# 140701_AriloTX_REV2_0_0.net
KiCad netlist of a schematic drawn in EAGLE
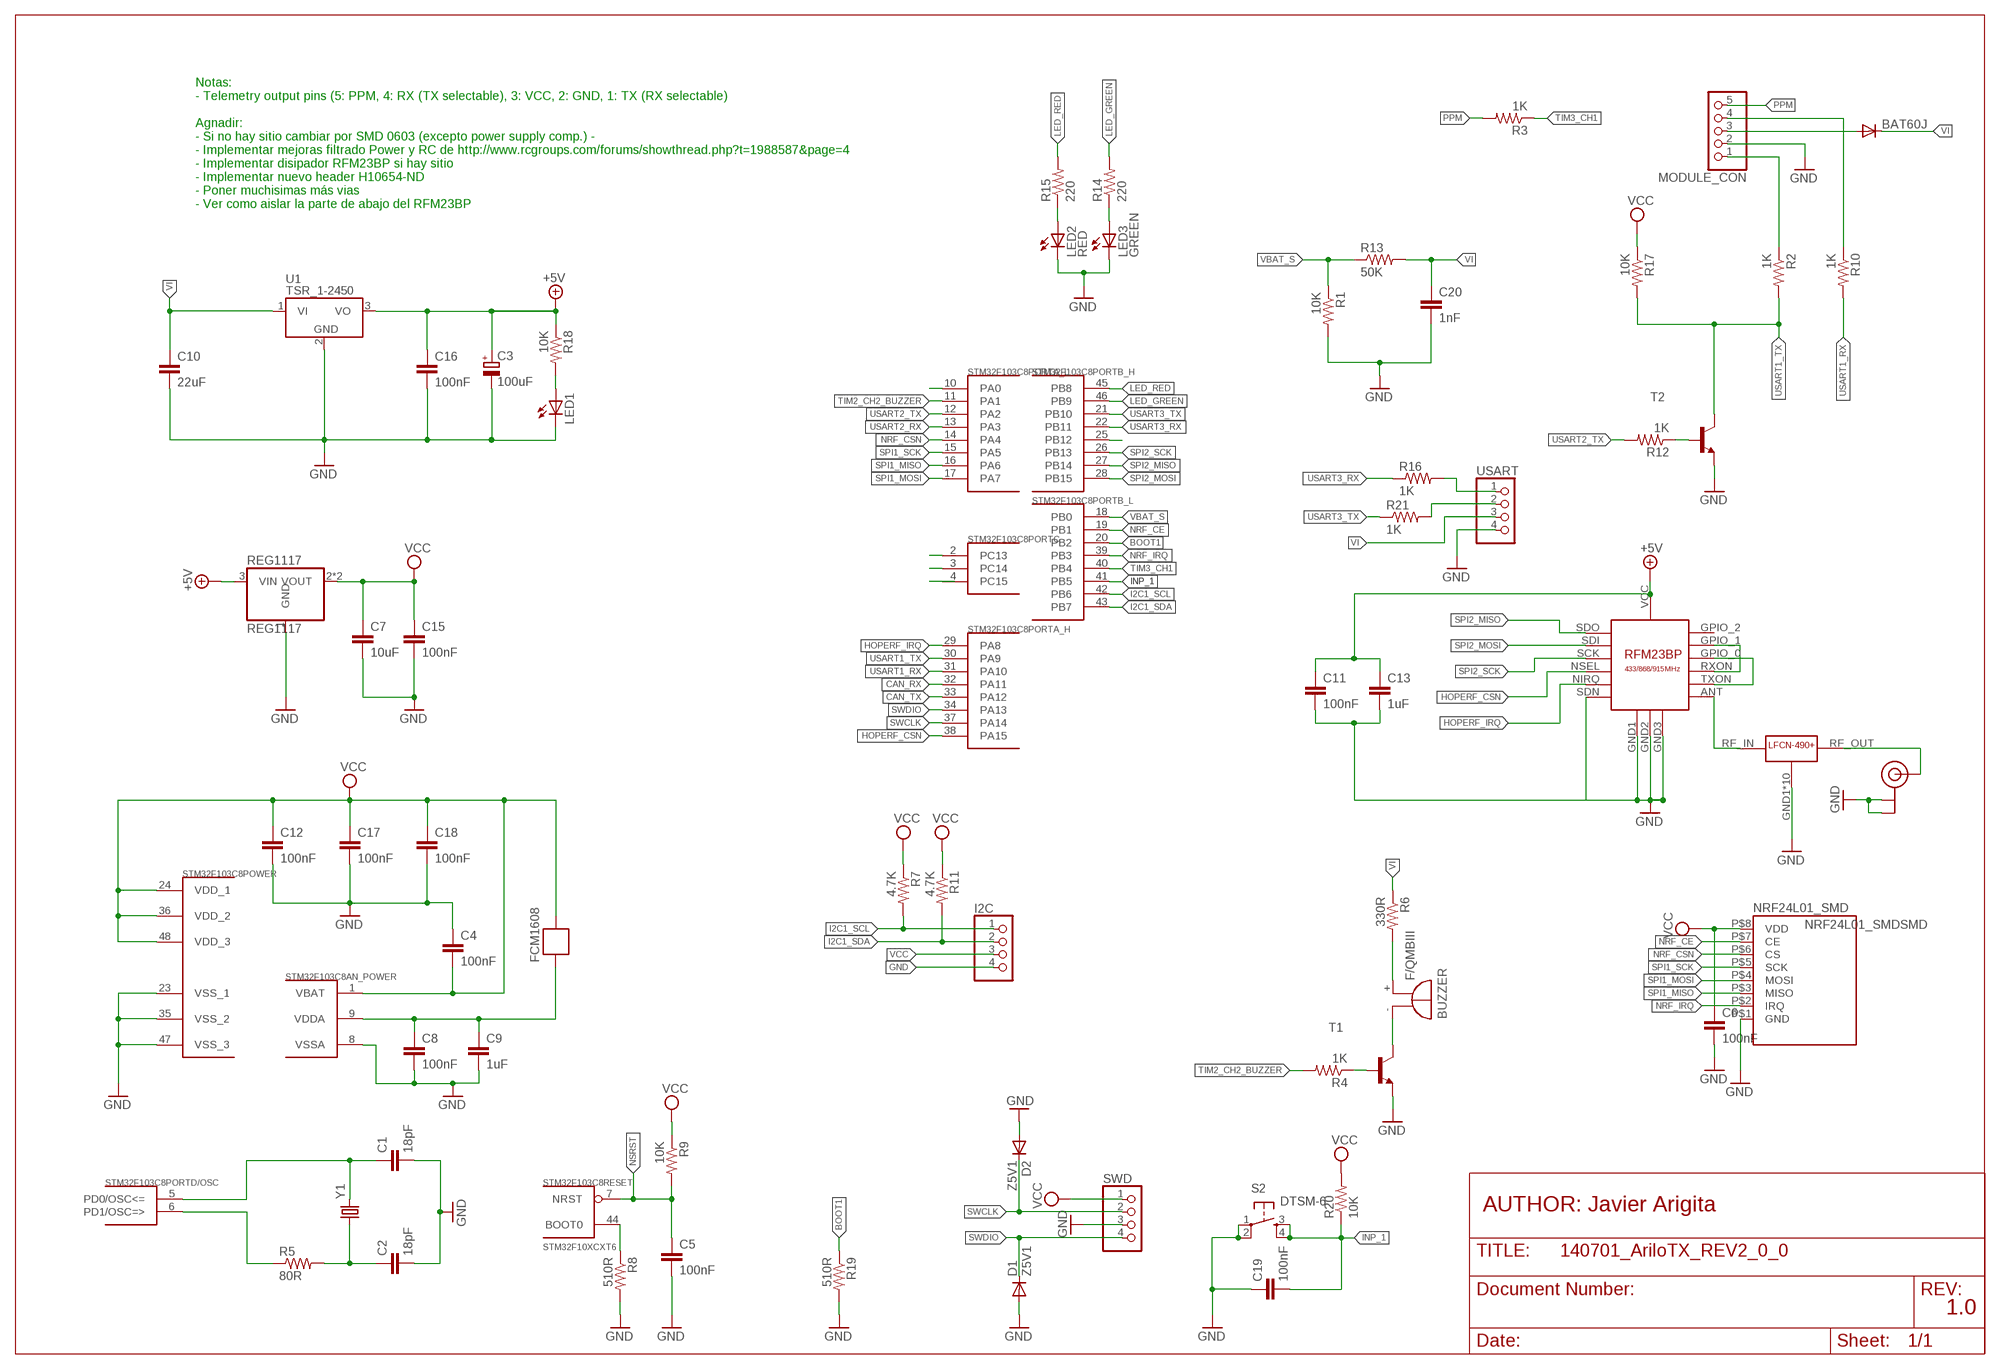
[diagram p0: schematic, sheet 1]

(export (version "E")
  (design (tool "Eeschema 10.0.6"))
  (components
    (comp (ref "BAT60J")
      (value "DIODE-SOD323-R")
      (footprint "eagle-import:SOD323-R")
      (libsource (lib "eagle-import") (part "DIODE-SOD323-R"))
    )
    (comp (ref "BUZZER")
      (value "F/QMBIII")
      (footprint "eagle-import:F_QMBIII")
      (libsource (lib "eagle-import") (part "F/QMBIII"))
    )
    (comp (ref "C1")
      (value "18pF")
      (footprint "eagle-import:C0805")
      (libsource (lib "eagle-import") (part "C-EUC0805"))
    )
    (comp (ref "C2")
      (value "18pF")
      (footprint "eagle-import:C0805")
      (libsource (lib "eagle-import") (part "C-EUC0805"))
    )
    (comp (ref "C3")
      (value "100uF")
      (footprint "eagle-import:SMC_B")
      (libsource (lib "eagle-import") (part "CPOL-EUSMCB"))
    )
    (comp (ref "C4")
      (value "100nF")
      (footprint "eagle-import:C0805")
      (libsource (lib "eagle-import") (part "C-EUC0805"))
    )
    (comp (ref "C5")
      (value "100nF")
      (footprint "eagle-import:C0805")
      (libsource (lib "eagle-import") (part "C-EUC0805"))
    )
    (comp (ref "C6")
      (value "100nF")
      (footprint "eagle-import:C0805")
      (libsource (lib "eagle-import") (part "C-EUC0805"))
    )
    (comp (ref "C7")
      (value "10uF")
      (footprint "eagle-import:C0805")
      (libsource (lib "eagle-import") (part "C-EUC0805"))
    )
    (comp (ref "C8")
      (value "100nF")
      (footprint "eagle-import:C0805")
      (libsource (lib "eagle-import") (part "C-EUC0805"))
    )
    (comp (ref "C9")
      (value "1uF")
      (footprint "eagle-import:C3216")
      (libsource (lib "eagle-import") (part "resistor_C-EUC3216"))
    )
    (comp (ref "C10")
      (value "22uF")
      (footprint "eagle-import:C3216")
      (libsource (lib "eagle-import") (part "resistor_C-EUC3216"))
    )
    (comp (ref "C11")
      (value "100nF")
      (footprint "eagle-import:C0805")
      (libsource (lib "eagle-import") (part "C-EUC0805"))
    )
    (comp (ref "C12")
      (value "100nF")
      (footprint "eagle-import:C0805")
      (libsource (lib "eagle-import") (part "C-EUC0805"))
    )
    (comp (ref "C13")
      (value "1uF")
      (footprint "eagle-import:C3216")
      (libsource (lib "eagle-import") (part "resistor_C-EUC3216"))
    )
    (comp (ref "C15")
      (value "100nF")
      (footprint "eagle-import:C0805")
      (libsource (lib "eagle-import") (part "C-EUC0805"))
    )
    (comp (ref "C16")
      (value "100nF")
      (footprint "eagle-import:C0805")
      (libsource (lib "eagle-import") (part "C-EUC0805"))
    )
    (comp (ref "C17")
      (value "100nF")
      (footprint "eagle-import:C0805")
      (libsource (lib "eagle-import") (part "C-EUC0805"))
    )
    (comp (ref "C18")
      (value "100nF")
      (footprint "eagle-import:C0805")
      (libsource (lib "eagle-import") (part "C-EUC0805"))
    )
    (comp (ref "C19")
      (value "100nF")
      (footprint "eagle-import:C0805")
      (libsource (lib "eagle-import") (part "C-EUC0805"))
    )
    (comp (ref "C20")
      (value "1nF")
      (footprint "eagle-import:C0805")
      (libsource (lib "eagle-import") (part "C-EUC0805"))
    )
    (comp (ref "D1")
      (value "Z5V1")
      (footprint "eagle-import:SOD323-R")
      (libsource (lib "eagle-import") (part "DIODE-SOD323-R"))
    )
    (comp (ref "D2")
      (value "Z5V1")
      (footprint "eagle-import:SOD323-R")
      (libsource (lib "eagle-import") (part "DIODE-SOD323-R"))
    )
    (comp (ref "FCM1608")
      (value "FERRITE-BEAD")
      (footprint "eagle-import:R0603")
      (libsource (lib "eagle-import") (part "FERRITE-BEAD"))
    )
    (comp (ref "I2C")
      (value "PINHD-1X4")
      (footprint "eagle-import:1X04")
      (libsource (lib "eagle-import") (part "PINHD-1X4"))
    )
    (comp (ref "LED1")
      (value "LED0805")
      (footprint "eagle-import:CHIPLED_0805")
      (libsource (lib "eagle-import") (part "LED0805"))
    )
    (comp (ref "LED2")
      (value "RED")
      (footprint "eagle-import:CHIP-LED0805")
      (libsource (lib "eagle-import") (part "LEDCHIP-LED0805"))
    )
    (comp (ref "LED3")
      (value "GREEN")
      (footprint "eagle-import:CHIP-LED0805")
      (libsource (lib "eagle-import") (part "LEDCHIP-LED0805"))
    )
    (comp (ref "MODULE_CON")
      (value "PINHD-1X5")
      (footprint "eagle-import:1X05")
      (libsource (lib "eagle-import") (part "PINHD-1X5"))
    )
    (comp (ref "NRF24L01_SMD")
      (value "NRF24L01_SMDSMD")
      (footprint "eagle-import:NRF24L01_SMD")
      (libsource (lib "eagle-import") (part "NRF24L01_SMDSMD"))
    )
    (comp (ref "R1")
      (value "10K")
      (footprint "eagle-import:R0805")
      (libsource (lib "eagle-import") (part "RESISTOR0805"))
    )
    (comp (ref "R2")
      (value "1K")
      (footprint "eagle-import:R0805")
      (libsource (lib "eagle-import") (part "RESISTOR0805"))
    )
    (comp (ref "R3")
      (value "1K")
      (footprint "eagle-import:R0805")
      (libsource (lib "eagle-import") (part "RESISTOR0805"))
    )
    (comp (ref "R4")
      (value "1K")
      (footprint "eagle-import:R0805")
      (libsource (lib "eagle-import") (part "RESISTOR0805"))
    )
    (comp (ref "R5")
      (value "80R")
      (footprint "eagle-import:R0805")
      (libsource (lib "eagle-import") (part "RESISTOR0805"))
    )
    (comp (ref "R6")
      (value "330R")
      (footprint "eagle-import:R0805")
      (libsource (lib "eagle-import") (part "RESISTOR0805"))
    )
    (comp (ref "R7")
      (value "4.7K")
      (footprint "eagle-import:R0805")
      (libsource (lib "eagle-import") (part "RESISTOR0805"))
    )
    (comp (ref "R8")
      (value "510R")
      (footprint "eagle-import:R0805")
      (libsource (lib "eagle-import") (part "RESISTOR0805"))
    )
    (comp (ref "R9")
      (value "10K")
      (footprint "eagle-import:R0805")
      (libsource (lib "eagle-import") (part "RESISTOR0805"))
    )
    (comp (ref "R10")
      (value "1K")
      (footprint "eagle-import:R0805")
      (libsource (lib "eagle-import") (part "RESISTOR0805"))
    )
    (comp (ref "R11")
      (value "4.7K")
      (footprint "eagle-import:R0805")
      (libsource (lib "eagle-import") (part "RESISTOR0805"))
    )
    (comp (ref "R12")
      (value "1K")
      (footprint "eagle-import:R0805")
      (libsource (lib "eagle-import") (part "RESISTOR0805"))
    )
    (comp (ref "R13")
      (value "50K")
      (footprint "eagle-import:R0805")
      (libsource (lib "eagle-import") (part "RESISTOR0805"))
    )
    (comp (ref "R14")
      (value "220")
      (footprint "eagle-import:R0805")
      (libsource (lib "eagle-import") (part "RESISTOR0805"))
    )
    (comp (ref "R15")
      (value "220")
      (footprint "eagle-import:R0805")
      (libsource (lib "eagle-import") (part "RESISTOR0805"))
    )
    (comp (ref "R16")
      (value "1K")
      (footprint "eagle-import:R0805")
      (libsource (lib "eagle-import") (part "RESISTOR0805"))
    )
    (comp (ref "R17")
      (value "10K")
      (footprint "eagle-import:R0805")
      (libsource (lib "eagle-import") (part "RESISTOR0805"))
    )
    (comp (ref "R18")
      (value "10K")
      (footprint "eagle-import:R0805")
      (libsource (lib "eagle-import") (part "RESISTOR0805"))
    )
    (comp (ref "R19")
      (value "510R")
      (footprint "eagle-import:R0805")
      (libsource (lib "eagle-import") (part "RESISTOR0805"))
    )
    (comp (ref "R20")
      (value "10K")
      (footprint "eagle-import:R0805")
      (libsource (lib "eagle-import") (part "RESISTOR0805"))
    )
    (comp (ref "R21")
      (value "1K")
      (footprint "eagle-import:R0805")
      (libsource (lib "eagle-import") (part "RESISTOR0805"))
    )
    (comp (ref "REG1117")
      (value "REG1117")
      (footprint "eagle-import:SOT223")
      (libsource (lib "eagle-import") (part "REG1117"))
    )
    (comp (ref "S2")
      (value "DTSM-6")
      (footprint "eagle-import:DTSM-6")
      (libsource (lib "eagle-import") (part "DTSM-6"))
    )
    (comp (ref "STM32F103C8")
      (value "STM32F10XCXT6")
      (footprint "eagle-import:TQFP48")
      (libsource (lib "eagle-import") (part "STM32F10XCXT6"))
    )
    (comp (ref "SWD")
      (value "PINHD-1X4")
      (footprint "eagle-import:1X04")
      (libsource (lib "eagle-import") (part "PINHD-1X4"))
    )
    (comp (ref "T1")
      (value "BC848-NPN-SOT23-BEC")
      (footprint "eagle-import:SOT23-BEC")
      (libsource (lib "eagle-import") (part "-NPN-SOT23-BECBC848"))
    )
    (comp (ref "T2")
      (value "BC848-NPN-SOT23-BEC")
      (footprint "eagle-import:SOT23-BEC")
      (libsource (lib "eagle-import") (part "-NPN-SOT23-BECBC848"))
    )
    (comp (ref "U$1")
      (value "RFM23BP")
      (footprint "eagle-import:RFM23BP")
      (libsource (lib "eagle-import") (part "RFM23BP"))
    )
    (comp (ref "U$2")
      (value "LFCN490+")
      (footprint "eagle-import:LFCN490+")
      (libsource (lib "eagle-import") (part "LFCN490+"))
    )
    (comp (ref "U$3")
      (value "U.FL")
      (footprint "eagle-import:U.FL")
      (libsource (lib "eagle-import") (part "U.FL"))
    )
    (comp (ref "U1")
      (value "TSR_1-2450")
      (footprint "eagle-import:TSR-1")
      (libsource (lib "eagle-import") (part "TSR_1-2450"))
    )
    (comp (ref "USART")
      (value "PINHD-1X4")
      (footprint "eagle-import:1X04")
      (libsource (lib "eagle-import") (part "PINHD-1X4"))
    )
    (comp (ref "Y1")
      (value "CRYSTAL5X3")
      (footprint "eagle-import:CRYSTAL-SMD-5X3")
      (libsource (lib "eagle-import") (part "CRYSTAL5X3"))
    )
  )
  (nets
    (net (code "1") (name "+5V") (class "Default")
      (node (ref "C11") (pin "1") (pinfunction "1_1") (pintype "passive"))
      (node (ref "C13") (pin "1") (pinfunction "1_1") (pintype "passive"))
      (node (ref "C16") (pin "1") (pinfunction "1_1") (pintype "passive"))
      (node (ref "C3") (pin "+") (pinfunction "+_+") (pintype "passive"))
      (node (ref "R18") (pin "1") (pinfunction "1_1") (pintype "passive"))
      (node (ref "REG1117") (pin "3") (pinfunction "VIN_3") (pintype "input"))
      (node (ref "U$1") (pin "VCC") (pinfunction "VCC_VCC") (pintype "power_in"))
      (node (ref "U1") (pin "3") (pinfunction "VO_3") (pintype "power_in"))
    )
    (net (code "2") (name "BOOT1") (class "Default")
      (node (ref "R19") (pin "1") (pinfunction "1_1") (pintype "passive"))
      (node (ref "STM32F103C8") (pin "20") (pinfunction "PB2_20") (pintype "bidirectional"))
    )
    (net (code "3") (name "CAN_RX") (class "Default")
      (node (ref "STM32F103C8") (pin "32") (pinfunction "PA11_32") (pintype "bidirectional"))
    )
    (net (code "4") (name "CAN_TX") (class "Default")
      (node (ref "STM32F103C8") (pin "33") (pinfunction "PA12_33") (pintype "bidirectional"))
    )
    (net (code "5") (name "GND") (class "Default")
      (node (ref "C1") (pin "2") (pinfunction "2_2") (pintype "passive"))
      (node (ref "C10") (pin "2") (pinfunction "2_2") (pintype "passive"))
      (node (ref "C11") (pin "2") (pinfunction "2_2") (pintype "passive"))
      (node (ref "C12") (pin "2") (pinfunction "2_2") (pintype "passive"))
      (node (ref "C13") (pin "2") (pinfunction "2_2") (pintype "passive"))
      (node (ref "C15") (pin "2") (pinfunction "2_2") (pintype "passive"))
      (node (ref "C16") (pin "2") (pinfunction "2_2") (pintype "passive"))
      (node (ref "C17") (pin "2") (pinfunction "2_2") (pintype "passive"))
      (node (ref "C18") (pin "2") (pinfunction "2_2") (pintype "passive"))
      (node (ref "C19") (pin "1") (pinfunction "1_1") (pintype "passive"))
      (node (ref "C2") (pin "2") (pinfunction "2_2") (pintype "passive"))
      (node (ref "C20") (pin "2") (pinfunction "2_2") (pintype "passive"))
      (node (ref "C3") (pin "-") (pinfunction "-_-") (pintype "passive"))
      (node (ref "C4") (pin "1") (pinfunction "1_1") (pintype "passive"))
      (node (ref "C5") (pin "2") (pinfunction "2_2") (pintype "passive"))
      (node (ref "C6") (pin "2") (pinfunction "2_2") (pintype "passive"))
      (node (ref "C7") (pin "2") (pinfunction "2_2") (pintype "passive"))
      (node (ref "C8") (pin "2") (pinfunction "2_2") (pintype "passive"))
      (node (ref "C9") (pin "2") (pinfunction "2_2") (pintype "passive"))
      (node (ref "D1") (pin "A") (pinfunction "A_A") (pintype "passive"))
      (node (ref "D2") (pin "A") (pinfunction "A_A") (pintype "passive"))
      (node (ref "I2C") (pin "4") (pinfunction "4_4") (pintype "passive"))
      (node (ref "LED1") (pin "C") (pinfunction "C_C") (pintype "passive"))
      (node (ref "LED2") (pin "C") (pinfunction "C_C") (pintype "passive"))
      (node (ref "LED3") (pin "C") (pinfunction "C_C") (pintype "passive"))
      (node (ref "MODULE_CON") (pin "2") (pinfunction "2_2") (pintype "passive"))
      (node (ref "NRF24L01_SMD") (pin "P$1") (pinfunction "GND_P$1") (pintype "power_in"))
      (node (ref "R1") (pin "2") (pinfunction "2_2") (pintype "passive"))
      (node (ref "R19") (pin "2") (pinfunction "2_2") (pintype "passive"))
      (node (ref "R8") (pin "2") (pinfunction "2_2") (pintype "passive"))
      (node (ref "REG1117") (pin "1") (pinfunction "GND_1") (pintype "power_in"))
      (node (ref "S2") (pin "1") (pinfunction "1_1") (pintype "passive"))
      (node (ref "S2") (pin "2") (pinfunction "2_2") (pintype "passive"))
      (node (ref "STM32F103C8") (pin "23") (pinfunction "VSS_1_23") (pintype "power_in"))
      (node (ref "STM32F103C8") (pin "35") (pinfunction "VSS_2_35") (pintype "power_in"))
      (node (ref "STM32F103C8") (pin "47") (pinfunction "VSS_3_47") (pintype "power_in"))
      (node (ref "STM32F103C8") (pin "8") (pinfunction "VSSA_8") (pintype "power_in"))
      (node (ref "SWD") (pin "3") (pinfunction "3_3") (pintype "passive"))
      (node (ref "T1") (pin "E") (pinfunction "E_E") (pintype "passive"))
      (node (ref "T2") (pin "E") (pinfunction "E_E") (pintype "passive"))
      (node (ref "U$1") (pin "GND1") (pinfunction "GND1_GND1") (pintype "power_in"))
      (node (ref "U$1") (pin "GND2") (pinfunction "GND2_GND2") (pintype "power_in"))
      (node (ref "U$1") (pin "GND3") (pinfunction "GND3_GND3") (pintype "power_in"))
      (node (ref "U$1") (pin "SDN") (pinfunction "SDN_SDN") (pintype "bidirectional"))
      (node (ref "U$2") (pin "GND1") (pinfunction "GND_GND1") (pintype "bidirectional"))
      (node (ref "U$2") (pin "GND10") (pinfunction "GND_GND10") (pintype "bidirectional"))
      (node (ref "U$2") (pin "GND2") (pinfunction "GND_GND2") (pintype "bidirectional"))
      (node (ref "U$2") (pin "GND3") (pinfunction "GND_GND3") (pintype "bidirectional"))
      (node (ref "U$2") (pin "GND4") (pinfunction "GND_GND4") (pintype "bidirectional"))
      (node (ref "U$2") (pin "GND5") (pinfunction "GND_GND5") (pintype "bidirectional"))
      (node (ref "U$2") (pin "GND6") (pinfunction "GND_GND6") (pintype "bidirectional"))
      (node (ref "U$2") (pin "GND7") (pinfunction "GND_GND7") (pintype "bidirectional"))
      (node (ref "U$2") (pin "GND8") (pinfunction "GND_GND8") (pintype "bidirectional"))
      (node (ref "U$2") (pin "GND9") (pinfunction "GND_GND9") (pintype "bidirectional"))
      (node (ref "U$3") (pin "P$1") (pinfunction "GND_P$1") (pintype "bidirectional"))
      (node (ref "U$3") (pin "P$2") (pinfunction "GND_P$2") (pintype "bidirectional"))
      (node (ref "U1") (pin "2") (pinfunction "GND_2") (pintype "power_in"))
      (node (ref "USART") (pin "4") (pinfunction "4_4") (pintype "passive"))
    )
    (net (code "6") (name "HOPERF_CSN") (class "Default")
      (node (ref "STM32F103C8") (pin "38") (pinfunction "PA15_38") (pintype "bidirectional"))
      (node (ref "U$1") (pin "NSEL") (pinfunction "NSEL_NSEL") (pintype "bidirectional"))
    )
    (net (code "7") (name "HOPERF_IRQ") (class "Default")
      (node (ref "STM32F103C8") (pin "29") (pinfunction "PA8_29") (pintype "bidirectional"))
      (node (ref "U$1") (pin "NIRQ") (pinfunction "NIRQ_NIRQ") (pintype "bidirectional"))
    )
    (net (code "8") (name "I2C1_SCL") (class "Default")
      (node (ref "I2C") (pin "1") (pinfunction "1_1") (pintype "passive"))
      (node (ref "R7") (pin "2") (pinfunction "2_2") (pintype "passive"))
      (node (ref "STM32F103C8") (pin "42") (pinfunction "PB6_42") (pintype "bidirectional"))
    )
    (net (code "9") (name "I2C1_SDA") (class "Default")
      (node (ref "I2C") (pin "2") (pinfunction "2_2") (pintype "passive"))
      (node (ref "R11") (pin "2") (pinfunction "2_2") (pintype "passive"))
      (node (ref "STM32F103C8") (pin "43") (pinfunction "PB7_43") (pintype "bidirectional"))
    )
    (net (code "10") (name "INP_1") (class "Default")
      (node (ref "C19") (pin "2") (pinfunction "2_2") (pintype "passive"))
      (node (ref "R20") (pin "1") (pinfunction "1_1") (pintype "passive"))
      (node (ref "S2") (pin "3") (pinfunction "3_3") (pintype "passive"))
      (node (ref "S2") (pin "4") (pinfunction "4_4") (pintype "passive"))
      (node (ref "STM32F103C8") (pin "41") (pinfunction "PB5_41") (pintype "bidirectional"))
    )
    (net (code "11") (name "LED_GREEN") (class "Default")
      (node (ref "R14") (pin "2") (pinfunction "2_2") (pintype "passive"))
      (node (ref "STM32F103C8") (pin "46") (pinfunction "PB9_46") (pintype "bidirectional"))
    )
    (net (code "12") (name "LED_RED") (class "Default")
      (node (ref "R15") (pin "2") (pinfunction "2_2") (pintype "passive"))
      (node (ref "STM32F103C8") (pin "45") (pinfunction "PB8_45") (pintype "bidirectional"))
    )
    (net (code "13") (name "NRF_CE") (class "Default")
      (node (ref "NRF24L01_SMD") (pin "P$7") (pinfunction "CE_P$7") (pintype "input"))
      (node (ref "STM32F103C8") (pin "19") (pinfunction "PB1_19") (pintype "bidirectional"))
    )
    (net (code "14") (name "NRF_CSN") (class "Default")
      (node (ref "NRF24L01_SMD") (pin "P$6") (pinfunction "CS_P$6") (pintype "input"))
      (node (ref "STM32F103C8") (pin "14") (pinfunction "PA4_14") (pintype "bidirectional"))
    )
    (net (code "15") (name "NRF_IRQ") (class "Default")
      (node (ref "NRF24L01_SMD") (pin "P$2") (pinfunction "IRQ_P$2") (pintype "output"))
      (node (ref "STM32F103C8") (pin "39") (pinfunction "PB3_39") (pintype "bidirectional"))
    )
    (net (code "16") (name "NSRST") (class "Default")
      (node (ref "C5") (pin "1") (pinfunction "1_1") (pintype "passive"))
      (node (ref "R9") (pin "2") (pinfunction "2_2") (pintype "passive"))
      (node (ref "STM32F103C8") (pin "7") (pinfunction "NRST_7") (pintype "input"))
    )
    (net (code "17") (name "Net-(BAT60J-PadA)") (class "Default")
      (node (ref "BAT60J") (pin "A") (pinfunction "A_A") (pintype "passive"))
      (node (ref "MODULE_CON") (pin "3") (pinfunction "3_3") (pintype "passive"))
    )
    (net (code "18") (name "Net-(BUZZER-+)") (class "Default")
      (node (ref "BUZZER") (pin "-") (pinfunction "+_-") (pintype "passive"))
      (node (ref "T1") (pin "C") (pinfunction "C_C") (pintype "passive"))
    )
    (net (code "19") (name "Net-(BUZZER--)") (class "Default")
      (node (ref "BUZZER") (pin "+") (pinfunction "-_+") (pintype "passive"))
      (node (ref "R6") (pin "2") (pinfunction "2_2") (pintype "passive"))
    )
    (net (code "20") (name "Net-(C2-Pad1)") (class "Default")
      (node (ref "C2") (pin "1") (pinfunction "1_1") (pintype "passive"))
      (node (ref "R5") (pin "2") (pinfunction "2_2") (pintype "passive"))
      (node (ref "Y1") (pin "1") (pinfunction "1_1") (pintype "passive"))
    )
    (net (code "21") (name "Net-(FCM1608-P$2)") (class "Default")
      (node (ref "C8") (pin "1") (pinfunction "1_1") (pintype "passive"))
      (node (ref "C9") (pin "1") (pinfunction "1_1") (pintype "passive"))
      (node (ref "FCM1608") (pin "2") (pinfunction "P$2_2") (pintype "bidirectional"))
      (node (ref "STM32F103C8") (pin "9") (pinfunction "VDDA_9") (pintype "power_in"))
    )
    (net (code "22") (name "Net-(LED1-PadA)") (class "Default")
      (node (ref "LED1") (pin "A") (pinfunction "A_A") (pintype "passive"))
      (node (ref "R18") (pin "2") (pinfunction "2_2") (pintype "passive"))
    )
    (net (code "23") (name "Net-(LED2-PadA)") (class "Default")
      (node (ref "LED2") (pin "A") (pinfunction "A_A") (pintype "passive"))
      (node (ref "R15") (pin "1") (pinfunction "1_1") (pintype "passive"))
    )
    (net (code "24") (name "Net-(LED3-PadA)") (class "Default")
      (node (ref "LED3") (pin "A") (pinfunction "A_A") (pintype "passive"))
      (node (ref "R14") (pin "1") (pinfunction "1_1") (pintype "passive"))
    )
    (net (code "25") (name "Net-(MODULE_CON-Pad1)") (class "Default")
      (node (ref "MODULE_CON") (pin "1") (pinfunction "1_1") (pintype "passive"))
      (node (ref "R2") (pin "1") (pinfunction "1_1") (pintype "passive"))
    )
    (net (code "26") (name "Net-(MODULE_CON-Pad4)") (class "Default")
      (node (ref "MODULE_CON") (pin "4") (pinfunction "4_4") (pintype "passive"))
      (node (ref "R10") (pin "1") (pinfunction "1_1") (pintype "passive"))
    )
    (net (code "27") (name "Net-(R4-Pad1)") (class "Default")
      (node (ref "R4") (pin "1") (pinfunction "1_1") (pintype "passive"))
      (node (ref "T1") (pin "B") (pinfunction "B_B") (pintype "passive"))
    )
    (net (code "28") (name "Net-(R12-Pad1)") (class "Default")
      (node (ref "R12") (pin "1") (pinfunction "1_1") (pintype "passive"))
      (node (ref "T2") (pin "B") (pinfunction "B_B") (pintype "passive"))
    )
    (net (code "29") (name "Net-(R16-Pad2)") (class "Default")
      (node (ref "R16") (pin "2") (pinfunction "2_2") (pintype "passive"))
      (node (ref "USART") (pin "1") (pinfunction "1_1") (pintype "passive"))
    )
    (net (code "30") (name "Net-(R21-Pad2)") (class "Default")
      (node (ref "R21") (pin "2") (pinfunction "2_2") (pintype "passive"))
      (node (ref "USART") (pin "2") (pinfunction "2_2") (pintype "passive"))
    )
    (net (code "31") (name "Net-(STM32F103C8G-PD0{slash}OSC<=)") (class "Default")
      (node (ref "C1") (pin "1") (pinfunction "1_1") (pintype "passive"))
      (node (ref "STM32F103C8") (pin "5") (pinfunction "PD0/OSC<=_5") (pintype "bidirectional"))
      (node (ref "Y1") (pin "3") (pinfunction "2_3") (pintype "passive"))
    )
    (net (code "32") (name "Net-(STM32F103C8G-PD1{slash}OSC=>)") (class "Default")
      (node (ref "R5") (pin "1") (pinfunction "1_1") (pintype "passive"))
      (node (ref "STM32F103C8") (pin "6") (pinfunction "PD1/OSC=>_6") (pintype "bidirectional"))
    )
    (net (code "33") (name "Net-(STM32F103C8I-BOOT0)") (class "Default")
      (node (ref "R8") (pin "1") (pinfunction "1_1") (pintype "passive"))
      (node (ref "STM32F103C8") (pin "44") (pinfunction "BOOT0_44") (pintype "input"))
    )
    (net (code "34") (name "Net-(U$1-PadGPIO_0)") (class "Default")
      (node (ref "U$1") (pin "GPIO_0") (pinfunction "GPIO_0_GPIO_0") (pintype "bidirectional"))
      (node (ref "U$1") (pin "TXON") (pinfunction "TXON_TXON") (pintype "bidirectional"))
    )
    (net (code "35") (name "Net-(U$1-PadGPIO_1)") (class "Default")
      (node (ref "U$1") (pin "GPIO_1") (pinfunction "GPIO_1_GPIO_1") (pintype "bidirectional"))
      (node (ref "U$1") (pin "RXON") (pinfunction "RXON_RXON") (pintype "bidirectional"))
    )
    (net (code "36") (name "Net-(U$2-RF_INP)") (class "Default")
      (node (ref "U$1") (pin "ANT") (pinfunction "ANT_ANT") (pintype "bidirectional"))
      (node (ref "U$2") (pin "RF_IN") (pinfunction "RF_INP_RF_IN") (pintype "bidirectional"))
    )
    (net (code "37") (name "Net-(U$2-RF_OUTP)") (class "Default")
      (node (ref "U$2") (pin "RF_OUT") (pinfunction "RF_OUTP_RF_OUT") (pintype "bidirectional"))
      (node (ref "U$3") (pin "P$3") (pinfunction "SIGNAL_P$3") (pintype "bidirectional"))
    )
    (net (code "38") (name "PPM") (class "Default")
      (node (ref "MODULE_CON") (pin "5") (pinfunction "5_5") (pintype "passive"))
      (node (ref "R3") (pin "2") (pinfunction "2_2") (pintype "passive"))
    )
    (net (code "39") (name "SPI1_MISO") (class "Default")
      (node (ref "NRF24L01_SMD") (pin "P$3") (pinfunction "MISO_P$3") (pintype "output"))
      (node (ref "STM32F103C8") (pin "16") (pinfunction "PA6_16") (pintype "bidirectional"))
    )
    (net (code "40") (name "SPI1_MOSI") (class "Default")
      (node (ref "NRF24L01_SMD") (pin "P$4") (pinfunction "MOSI_P$4") (pintype "input"))
      (node (ref "STM32F103C8") (pin "17") (pinfunction "PA7_17") (pintype "bidirectional"))
    )
    (net (code "41") (name "SPI1_SCK") (class "Default")
      (node (ref "NRF24L01_SMD") (pin "P$5") (pinfunction "SCK_P$5") (pintype "input"))
      (node (ref "STM32F103C8") (pin "15") (pinfunction "PA5_15") (pintype "bidirectional"))
    )
    (net (code "42") (name "SPI2_MISO") (class "Default")
      (node (ref "STM32F103C8") (pin "27") (pinfunction "PB14_27") (pintype "bidirectional"))
      (node (ref "U$1") (pin "SDO") (pinfunction "SDO_SDO") (pintype "bidirectional"))
    )
    (net (code "43") (name "SPI2_MOSI") (class "Default")
      (node (ref "STM32F103C8") (pin "28") (pinfunction "PB15_28") (pintype "bidirectional"))
      (node (ref "U$1") (pin "SDI") (pinfunction "SDI_SDI") (pintype "bidirectional"))
    )
    (net (code "44") (name "SPI2_SCK") (class "Default")
      (node (ref "STM32F103C8") (pin "26") (pinfunction "PB13_26") (pintype "bidirectional"))
      (node (ref "U$1") (pin "SCK") (pinfunction "SCK_SCK") (pintype "bidirectional"))
    )
    (net (code "45") (name "SWCLK") (class "Default")
      (node (ref "D2") (pin "C") (pinfunction "C_C") (pintype "passive"))
      (node (ref "STM32F103C8") (pin "37") (pinfunction "PA14_37") (pintype "bidirectional"))
      (node (ref "SWD") (pin "2") (pinfunction "2_2") (pintype "passive"))
    )
    (net (code "46") (name "SWDIO") (class "Default")
      (node (ref "D1") (pin "C") (pinfunction "C_C") (pintype "passive"))
      (node (ref "STM32F103C8") (pin "34") (pinfunction "PA13_34") (pintype "bidirectional"))
      (node (ref "SWD") (pin "4") (pinfunction "4_4") (pintype "passive"))
    )
    (net (code "47") (name "TIM2_CH2_BUZZER") (class "Default")
      (node (ref "R4") (pin "2") (pinfunction "2_2") (pintype "passive"))
      (node (ref "STM32F103C8") (pin "11") (pinfunction "PA1_11") (pintype "bidirectional"))
    )
    (net (code "48") (name "TIM3_CH1") (class "Default")
      (node (ref "R3") (pin "1") (pinfunction "1_1") (pintype "passive"))
      (node (ref "STM32F103C8") (pin "40") (pinfunction "PB4_40") (pintype "bidirectional"))
    )
    (net (code "49") (name "USART1_RX") (class "Default")
      (node (ref "R10") (pin "2") (pinfunction "2_2") (pintype "passive"))
      (node (ref "STM32F103C8") (pin "31") (pinfunction "PA10_31") (pintype "bidirectional"))
    )
    (net (code "50") (name "USART1_TX") (class "Default")
      (node (ref "R17") (pin "2") (pinfunction "2_2") (pintype "passive"))
      (node (ref "R2") (pin "2") (pinfunction "2_2") (pintype "passive"))
      (node (ref "STM32F103C8") (pin "30") (pinfunction "PA9_30") (pintype "bidirectional"))
      (node (ref "T2") (pin "C") (pinfunction "C_C") (pintype "passive"))
    )
    (net (code "51") (name "USART2_RX") (class "Default")
      (node (ref "STM32F103C8") (pin "13") (pinfunction "PA3_13") (pintype "bidirectional"))
    )
    (net (code "52") (name "USART2_TX") (class "Default")
      (node (ref "R12") (pin "2") (pinfunction "2_2") (pintype "passive"))
      (node (ref "STM32F103C8") (pin "12") (pinfunction "PA2_12") (pintype "bidirectional"))
    )
    (net (code "53") (name "USART3_RX") (class "Default")
      (node (ref "R16") (pin "1") (pinfunction "1_1") (pintype "passive"))
      (node (ref "STM32F103C8") (pin "22") (pinfunction "PB11_22") (pintype "bidirectional"))
    )
    (net (code "54") (name "USART3_TX") (class "Default")
      (node (ref "R21") (pin "1") (pinfunction "1_1") (pintype "passive"))
      (node (ref "STM32F103C8") (pin "21") (pinfunction "PB10_21") (pintype "bidirectional"))
    )
    (net (code "55") (name "VBAT_S") (class "Default")
      (node (ref "R1") (pin "1") (pinfunction "1_1") (pintype "passive"))
      (node (ref "R13") (pin "1") (pinfunction "1_1") (pintype "passive"))
      (node (ref "STM32F103C8") (pin "18") (pinfunction "PB0_18") (pintype "bidirectional"))
    )
    (net (code "56") (name "VCC") (class "Default")
      (node (ref "C12") (pin "1") (pinfunction "1_1") (pintype "passive"))
      (node (ref "C15") (pin "1") (pinfunction "1_1") (pintype "passive"))
      (node (ref "C17") (pin "1") (pinfunction "1_1") (pintype "passive"))
      (node (ref "C18") (pin "1") (pinfunction "1_1") (pintype "passive"))
      (node (ref "C4") (pin "2") (pinfunction "2_2") (pintype "passive"))
      (node (ref "C6") (pin "1") (pinfunction "1_1") (pintype "passive"))
      (node (ref "C7") (pin "1") (pinfunction "1_1") (pintype "passive"))
      (node (ref "FCM1608") (pin "1") (pinfunction "P$1_1") (pintype "bidirectional"))
      (node (ref "I2C") (pin "3") (pinfunction "3_3") (pintype "passive"))
      (node (ref "NRF24L01_SMD") (pin "P$8") (pinfunction "VDD_P$8") (pintype "bidirectional"))
      (node (ref "R11") (pin "1") (pinfunction "1_1") (pintype "passive"))
      (node (ref "R17") (pin "1") (pinfunction "1_1") (pintype "passive"))
      (node (ref "R20") (pin "2") (pinfunction "2_2") (pintype "passive"))
      (node (ref "R7") (pin "1") (pinfunction "1_1") (pintype "passive"))
      (node (ref "R9") (pin "1") (pinfunction "1_1") (pintype "passive"))
      (node (ref "REG1117") (pin "2") (pinfunction "VOUT_2") (pintype "power_in"))
      (node (ref "REG1117") (pin "4") (pinfunction "VOUT_4") (pintype "power_in"))
      (node (ref "STM32F103C8") (pin "1") (pinfunction "VBAT_1") (pintype "power_in"))
      (node (ref "STM32F103C8") (pin "24") (pinfunction "VDD_1_24") (pintype "power_in"))
      (node (ref "STM32F103C8") (pin "36") (pinfunction "VDD_2_36") (pintype "power_in"))
      (node (ref "STM32F103C8") (pin "48") (pinfunction "VDD_3_48") (pintype "power_in"))
      (node (ref "SWD") (pin "1") (pinfunction "1_1") (pintype "passive"))
    )
    (net (code "57") (name "VI") (class "Default")
      (node (ref "BAT60J") (pin "C") (pinfunction "C_C") (pintype "passive"))
      (node (ref "C10") (pin "1") (pinfunction "1_1") (pintype "passive"))
      (node (ref "C20") (pin "1") (pinfunction "1_1") (pintype "passive"))
      (node (ref "R13") (pin "2") (pinfunction "2_2") (pintype "passive"))
      (node (ref "R6") (pin "1") (pinfunction "1_1") (pintype "passive"))
      (node (ref "U1") (pin "1") (pinfunction "VI_1") (pintype "power_in"))
      (node (ref "USART") (pin "3") (pinfunction "3_3") (pintype "passive"))
    )
    (net (code "58") (name "unconnected-(STM32F103C8C-PA0-Pad10)") (class "Default")
      (node (ref "STM32F103C8") (pin "10") (pinfunction "PA0_10") (pintype "bidirectional"))
    )
    (net (code "59") (name "unconnected-(STM32F103C8D-PB12-Pad25)") (class "Default")
      (node (ref "STM32F103C8") (pin "25") (pinfunction "PB12_25") (pintype "bidirectional"))
    )
    (net (code "60") (name "unconnected-(STM32F103C8F-PC13-Pad2)") (class "Default")
      (node (ref "STM32F103C8") (pin "2") (pinfunction "PC13_2") (pintype "bidirectional"))
    )
    (net (code "61") (name "unconnected-(STM32F103C8F-PC14-Pad3)") (class "Default")
      (node (ref "STM32F103C8") (pin "3") (pinfunction "PC14_3") (pintype "bidirectional"))
    )
    (net (code "62") (name "unconnected-(STM32F103C8F-PC15-Pad4)") (class "Default")
      (node (ref "STM32F103C8") (pin "4") (pinfunction "PC15_4") (pintype "bidirectional"))
    )
    (net (code "63") (name "unconnected-(U$1-PadGPIO_2)") (class "Default")
      (node (ref "U$1") (pin "GPIO_2") (pinfunction "GPIO_2_GPIO_2") (pintype "bidirectional"))
    )
  )
)
